# mySatellite.net
KiCad netlist of a schematic drawn in EAGLE
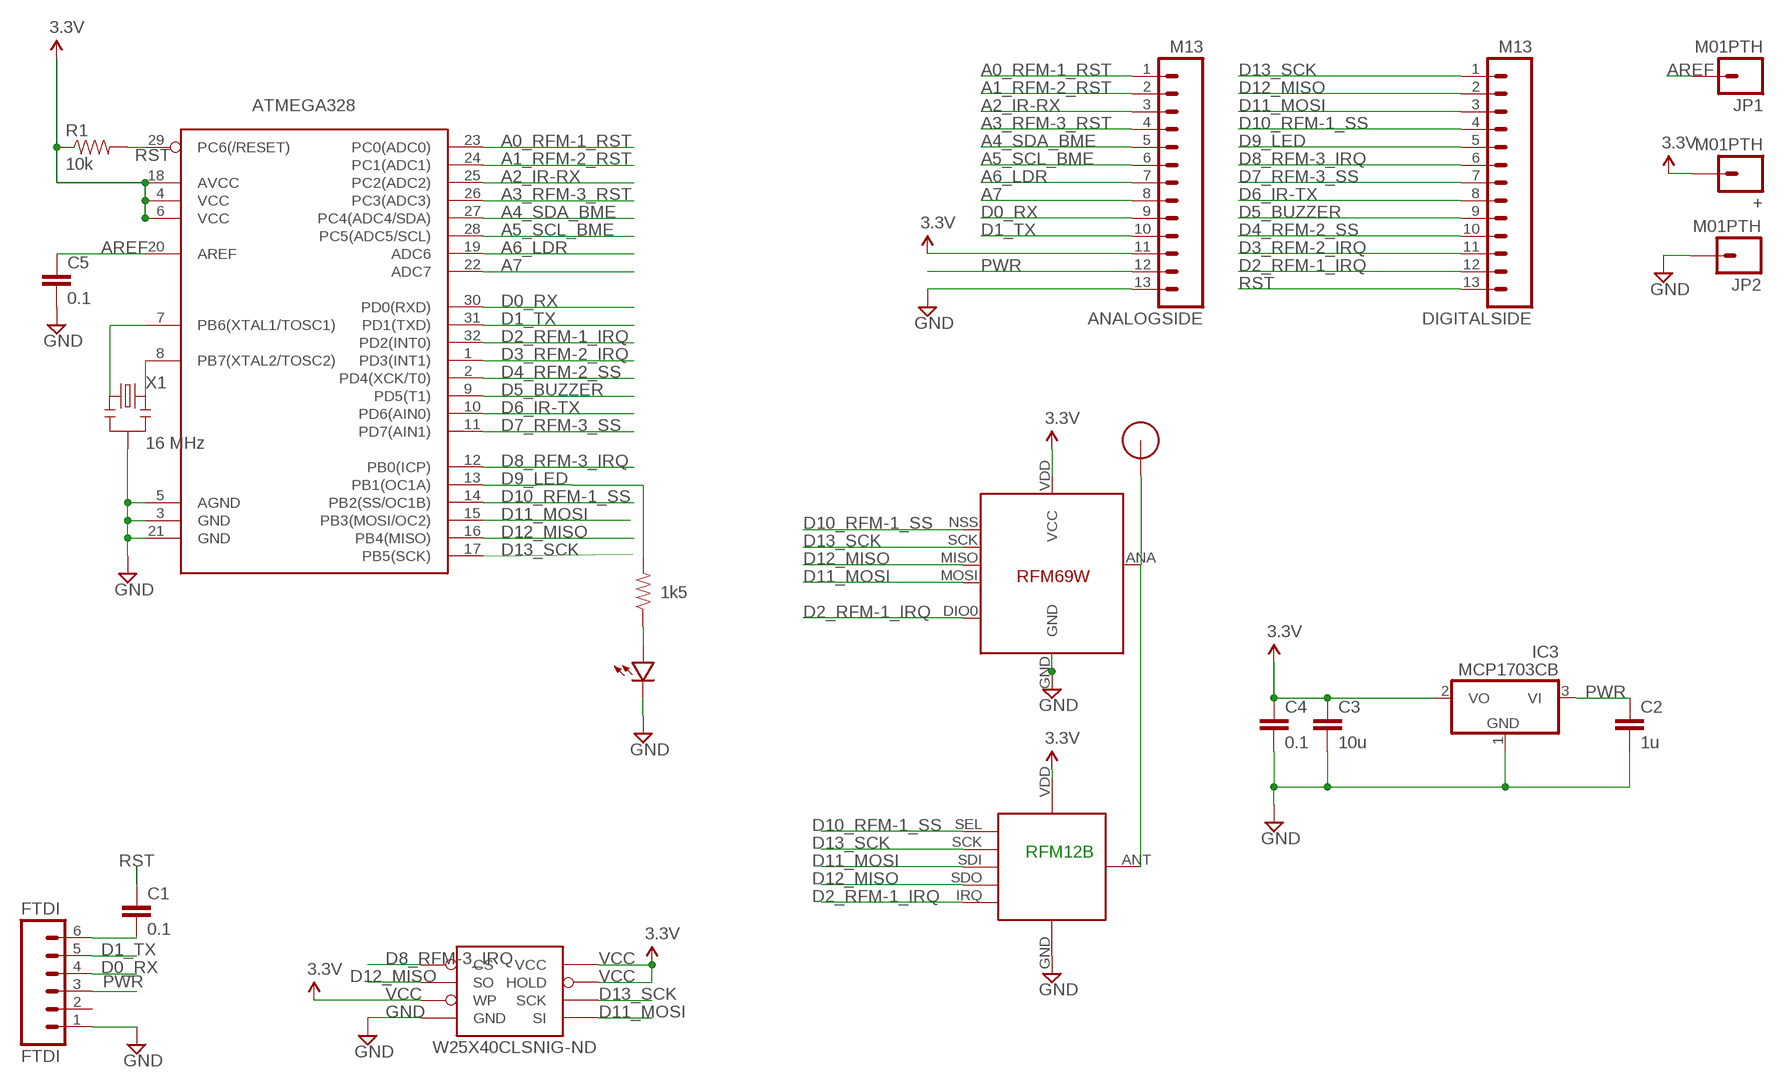
[diagram p0: schematic, sheet 1]

(export (version "E")
  (design (tool "Eeschema 10.0.6"))
  (components
    (comp (ref "+")
      (value "M01PTH")
      (footprint "eagle-import:1X01")
      (libsource (lib "eagle-import") (part "M01PTH"))
    )
    (comp (ref "ANALOGSIDE")
      (value "M13")
      (footprint "eagle-import:1X13")
      (libsource (lib "eagle-import") (part "M13"))
    )
    (comp (ref "ATMEGA328")
      (value "ATMega-328")
      (footprint "eagle-import:TQFP32-08")
      (libsource (lib "eagle-import") (part "ATMEGA168/328TQFP32"))
    )
    (comp (ref "C1")
      (value "0.1")
      (footprint "eagle-import:0603-CAP")
      (libsource (lib "eagle-import") (part "CAP0603-CAP"))
    )
    (comp (ref "C2")
      (value "1u")
      (footprint "eagle-import:0603-CAP")
      (libsource (lib "eagle-import") (part "CAP0603-CAP"))
    )
    (comp (ref "C3")
      (value "10u")
      (footprint "eagle-import:0805-CAP")
      (libsource (lib "eagle-import") (part "CAP0805-CAP"))
    )
    (comp (ref "C4")
      (value "0.1")
      (footprint "eagle-import:0603-CAP")
      (libsource (lib "eagle-import") (part "CAP0603-CAP"))
    )
    (comp (ref "C5")
      (value "0.1")
      (footprint "eagle-import:0603-CAP")
      (libsource (lib "eagle-import") (part "CAP0603-CAP"))
    )
    (comp (ref "DIGITALSIDE")
      (value "M13")
      (footprint "eagle-import:1X13")
      (libsource (lib "eagle-import") (part "M13"))
    )
    (comp (ref "FTDI")
      (value "FTDI")
      (footprint "eagle-import:1X06")
      (libsource (lib "eagle-import") (part "M06SIP"))
    )
    (comp (ref "IC3")
      (value "MCP1703CB")
      (footprint "eagle-import:SOT23")
      (libsource (lib "eagle-import") (part "MCP1703CB"))
    )
    (comp (ref "JP1")
      (value "M01PTH")
      (footprint "eagle-import:1X01")
      (libsource (lib "eagle-import") (part "M01PTH"))
    )
    (comp (ref "JP2")
      (value "M01PTH")
      (footprint "eagle-import:1X01")
      (libsource (lib "eagle-import") (part "M01PTH"))
    )
    (comp (ref "R1")
      (value "10k")
      (footprint "eagle-import:0603-RES")
      (libsource (lib "eagle-import") (part "RESISTOR0603-RES"))
    )
    (comp (ref "R2")
      (value "1k5")
      (footprint "eagle-import:0603-RES")
      (libsource (lib "eagle-import") (part "RESISTOR0603-RES"))
    )
    (comp (ref "RFM12B")
      (value "RFM12B_MINPADS")
      (footprint "eagle-import:RFM12B-MINPADS")
      (libsource (lib "eagle-import") (part "RFM12B_MINPADS"))
    )
    (comp (ref "U$1")
      (value "RFM12B_ANTENNA")
      (footprint "eagle-import:RFM12B-ANTENNA")
      (libsource (lib "eagle-import") (part "RFM12B_ANTENNA"))
    )
    (comp (ref "U$2")
      (value "LED0603")
      (footprint "eagle-import:0603-LED")
      (libsource (lib "eagle-import") (part "LED0603"))
    )
    (comp (ref "U$5")
      (value "RFM69")
      (footprint "eagle-import:RFM69W-MINPADS")
      (libsource (lib "eagle-import") (part "RFM69"))
    )
    (comp (ref "W25X40CLSNIG-ND")
      (value "AT25F512BWIDE_5.3MM")
      (footprint "eagle-import:SO08WIDE")
      (libsource (lib "eagle-import") (part "AT25F512BWIDE_5.3MM"))
    )
    (comp (ref "X1")
      (value "16 MHz")
      (footprint "eagle-import:RESONATOR-SMD")
      (libsource (lib "eagle-import") (part "RESONATORSMD"))
    )
  )
  (nets
    (net (code "1") (name "/A0_RFM-1_RST") (class "Default")
      (node (ref "ANALOGSIDE") (pin "1") (pinfunction "1_1") (pintype "passive"))
      (node (ref "ATMEGA328") (pin "23") (pinfunction "PC0(ADC0)_23") (pintype "bidirectional"))
    )
    (net (code "2") (name "/A1_RFM-2_RST") (class "Default")
      (node (ref "ANALOGSIDE") (pin "2") (pinfunction "2_2") (pintype "passive"))
      (node (ref "ATMEGA328") (pin "24") (pinfunction "PC1(ADC1)_24") (pintype "bidirectional"))
    )
    (net (code "3") (name "/A2_IR-RX") (class "Default")
      (node (ref "ANALOGSIDE") (pin "3") (pinfunction "3_3") (pintype "passive"))
      (node (ref "ATMEGA328") (pin "25") (pinfunction "PC2(ADC2)_25") (pintype "bidirectional"))
    )
    (net (code "4") (name "/A3_RFM-3_RST") (class "Default")
      (node (ref "ANALOGSIDE") (pin "4") (pinfunction "4_4") (pintype "passive"))
      (node (ref "ATMEGA328") (pin "26") (pinfunction "PC3(ADC3)_26") (pintype "bidirectional"))
    )
    (net (code "5") (name "/A4_SDA_BME") (class "Default")
      (node (ref "ANALOGSIDE") (pin "5") (pinfunction "5_5") (pintype "passive"))
      (node (ref "ATMEGA328") (pin "27") (pinfunction "PC4(ADC4/SDA)_27") (pintype "bidirectional"))
    )
    (net (code "6") (name "/A5_SCL_BME") (class "Default")
      (node (ref "ANALOGSIDE") (pin "6") (pinfunction "6_6") (pintype "passive"))
      (node (ref "ATMEGA328") (pin "28") (pinfunction "PC5(ADC5/SCL)_28") (pintype "bidirectional"))
    )
    (net (code "7") (name "/A6_LDR") (class "Default")
      (node (ref "ANALOGSIDE") (pin "7") (pinfunction "7_7") (pintype "passive"))
      (node (ref "ATMEGA328") (pin "19") (pinfunction "ADC6_19") (pintype "bidirectional"))
    )
    (net (code "8") (name "/A7") (class "Default")
      (node (ref "ANALOGSIDE") (pin "8") (pinfunction "8_8") (pintype "passive"))
      (node (ref "ATMEGA328") (pin "22") (pinfunction "ADC7_22") (pintype "bidirectional"))
    )
    (net (code "9") (name "/AREF") (class "Default")
      (node (ref "ATMEGA328") (pin "20") (pinfunction "AREF_20") (pintype "bidirectional"))
      (node (ref "C5") (pin "1") (pinfunction "1_1") (pintype "passive"))
      (node (ref "JP1") (pin "1") (pinfunction "1_1") (pintype "passive"))
    )
    (net (code "10") (name "/D0_RX") (class "Default")
      (node (ref "ANALOGSIDE") (pin "9") (pinfunction "9_9") (pintype "passive"))
      (node (ref "ATMEGA328") (pin "30") (pinfunction "PD0(RXD)_30") (pintype "bidirectional"))
      (node (ref "FTDI") (pin "4") (pinfunction "4_4") (pintype "passive"))
    )
    (net (code "11") (name "/D1_TX") (class "Default")
      (node (ref "ANALOGSIDE") (pin "10") (pinfunction "10_10") (pintype "passive"))
      (node (ref "ATMEGA328") (pin "31") (pinfunction "PD1(TXD)_31") (pintype "bidirectional"))
      (node (ref "FTDI") (pin "5") (pinfunction "5_5") (pintype "passive"))
    )
    (net (code "12") (name "/D2_RFM-1_IRQ") (class "Default")
      (node (ref "ATMEGA328") (pin "32") (pinfunction "PD2(INT0)_32") (pintype "bidirectional"))
      (node (ref "DIGITALSIDE") (pin "12") (pinfunction "12_12") (pintype "passive"))
      (node (ref "RFM12B") (pin "IRQ") (pinfunction "IRQ_IRQ") (pintype "bidirectional"))
      (node (ref "U$5") (pin "DIO0") (pinfunction "DIO0_DIO0") (pintype "open_collector"))
    )
    (net (code "13") (name "/D3_RFM-2_IRQ") (class "Default")
      (node (ref "ATMEGA328") (pin "1") (pinfunction "PD3(INT1)_1") (pintype "bidirectional"))
      (node (ref "DIGITALSIDE") (pin "11") (pinfunction "11_11") (pintype "passive"))
    )
    (net (code "14") (name "/D4_RFM-2_SS") (class "Default")
      (node (ref "ATMEGA328") (pin "2") (pinfunction "PD4(XCK/T0)_2") (pintype "bidirectional"))
      (node (ref "DIGITALSIDE") (pin "10") (pinfunction "10_10") (pintype "passive"))
    )
    (net (code "15") (name "/D5_BUZZER") (class "Default")
      (node (ref "ATMEGA328") (pin "9") (pinfunction "PD5(T1)_9") (pintype "bidirectional"))
      (node (ref "DIGITALSIDE") (pin "9") (pinfunction "9_9") (pintype "passive"))
    )
    (net (code "16") (name "/D6_IR-TX") (class "Default")
      (node (ref "ATMEGA328") (pin "10") (pinfunction "PD6(AIN0)_10") (pintype "bidirectional"))
      (node (ref "DIGITALSIDE") (pin "8") (pinfunction "8_8") (pintype "passive"))
    )
    (net (code "17") (name "/D7_RFM-3_SS") (class "Default")
      (node (ref "ATMEGA328") (pin "11") (pinfunction "PD7(AIN1)_11") (pintype "bidirectional"))
      (node (ref "DIGITALSIDE") (pin "7") (pinfunction "7_7") (pintype "passive"))
    )
    (net (code "18") (name "/D8_RFM-3_IRQ") (class "Default")
      (node (ref "ATMEGA328") (pin "12") (pinfunction "PB0(ICP)_12") (pintype "bidirectional"))
      (node (ref "DIGITALSIDE") (pin "6") (pinfunction "6_6") (pintype "passive"))
      (node (ref "W25X40CLSNIG-ND") (pin "1") (pinfunction "CS_1") (pintype "bidirectional"))
    )
    (net (code "19") (name "/D9_LED") (class "Default")
      (node (ref "ATMEGA328") (pin "13") (pinfunction "PB1(OC1A)_13") (pintype "bidirectional"))
      (node (ref "DIGITALSIDE") (pin "5") (pinfunction "5_5") (pintype "passive"))
      (node (ref "R2") (pin "2") (pinfunction "2_2") (pintype "passive"))
    )
    (net (code "20") (name "/D10_RFM-1_SS") (class "Default")
      (node (ref "ATMEGA328") (pin "14") (pinfunction "PB2(SS/OC1B)_14") (pintype "bidirectional"))
      (node (ref "DIGITALSIDE") (pin "4") (pinfunction "4_4") (pintype "passive"))
      (node (ref "RFM12B") (pin "SEL") (pinfunction "SEL_SEL") (pintype "bidirectional"))
      (node (ref "U$5") (pin "NSS") (pinfunction "SEL_NSS") (pintype "input"))
    )
    (net (code "21") (name "/D11_MOSI") (class "Default")
      (node (ref "ATMEGA328") (pin "15") (pinfunction "PB3(MOSI/OC2)_15") (pintype "bidirectional"))
      (node (ref "DIGITALSIDE") (pin "3") (pinfunction "3_3") (pintype "passive"))
      (node (ref "RFM12B") (pin "SDI") (pinfunction "SDI/MOSI_SDI") (pintype "bidirectional"))
      (node (ref "U$5") (pin "MOSI") (pinfunction "MOSI_MOSI") (pintype "output"))
      (node (ref "W25X40CLSNIG-ND") (pin "5") (pinfunction "SI_5") (pintype "bidirectional"))
    )
    (net (code "22") (name "/D12_MISO") (class "Default")
      (node (ref "ATMEGA328") (pin "16") (pinfunction "PB4(MISO)_16") (pintype "bidirectional"))
      (node (ref "DIGITALSIDE") (pin "2") (pinfunction "2_2") (pintype "passive"))
      (node (ref "RFM12B") (pin "SDO") (pinfunction "SDO/MISO_SDO") (pintype "bidirectional"))
      (node (ref "U$5") (pin "MISO") (pinfunction "MISO_MISO") (pintype "input"))
      (node (ref "W25X40CLSNIG-ND") (pin "2") (pinfunction "SO_2") (pintype "bidirectional"))
    )
    (net (code "23") (name "/D13_SCK") (class "Default")
      (node (ref "ATMEGA328") (pin "17") (pinfunction "PB5(SCK)_17") (pintype "bidirectional"))
      (node (ref "DIGITALSIDE") (pin "1") (pinfunction "1_1") (pintype "passive"))
      (node (ref "RFM12B") (pin "SCK") (pinfunction "SCK_SCK") (pintype "bidirectional"))
      (node (ref "U$5") (pin "SCK") (pinfunction "SCK_SCK") (pintype "input"))
      (node (ref "W25X40CLSNIG-ND") (pin "6") (pinfunction "SCK_6") (pintype "bidirectional"))
    )
    (net (code "24") (name "/PWR") (class "Default")
      (node (ref "ANALOGSIDE") (pin "12") (pinfunction "12_12") (pintype "passive"))
      (node (ref "C2") (pin "1") (pinfunction "1_1") (pintype "passive"))
      (node (ref "FTDI") (pin "3") (pinfunction "3_3") (pintype "passive"))
      (node (ref "IC3") (pin "3") (pinfunction "VI_3") (pintype "input"))
    )
    (net (code "25") (name "/RST") (class "Default")
      (node (ref "ATMEGA328") (pin "29") (pinfunction "PC6(/RESET)_29") (pintype "bidirectional"))
      (node (ref "C1") (pin "1") (pinfunction "1_1") (pintype "passive"))
      (node (ref "DIGITALSIDE") (pin "13") (pinfunction "13_13") (pintype "passive"))
      (node (ref "R1") (pin "2") (pinfunction "2_2") (pintype "passive"))
    )
    (net (code "26") (name "3.3V") (class "Default")
      (node (ref "+") (pin "1") (pinfunction "1_1") (pintype "passive"))
      (node (ref "ANALOGSIDE") (pin "11") (pinfunction "11_11") (pintype "passive"))
      (node (ref "ATMEGA328") (pin "18") (pinfunction "AVCC_18") (pintype "bidirectional"))
      (node (ref "ATMEGA328") (pin "4") (pinfunction "VCC_4") (pintype "bidirectional"))
      (node (ref "ATMEGA328") (pin "6") (pinfunction "VCC_6") (pintype "bidirectional"))
      (node (ref "C3") (pin "1") (pinfunction "1_1") (pintype "passive"))
      (node (ref "C4") (pin "1") (pinfunction "1_1") (pintype "passive"))
      (node (ref "IC3") (pin "2") (pinfunction "VO_2") (pintype "passive"))
      (node (ref "R1") (pin "1") (pinfunction "1_1") (pintype "passive"))
      (node (ref "RFM12B") (pin "VDD") (pinfunction "VDD_VDD") (pintype "bidirectional"))
      (node (ref "U$5") (pin "VDD") (pinfunction "VCC_VDD") (pintype "power_in"))
      (node (ref "W25X40CLSNIG-ND") (pin "3") (pinfunction "WP_3") (pintype "bidirectional"))
      (node (ref "W25X40CLSNIG-ND") (pin "7") (pinfunction "HOLD_7") (pintype "bidirectional"))
      (node (ref "W25X40CLSNIG-ND") (pin "8") (pinfunction "VCC_8") (pintype "bidirectional"))
    )
    (net (code "27") (name "GND") (class "Default")
      (node (ref "ANALOGSIDE") (pin "13") (pinfunction "13_13") (pintype "passive"))
      (node (ref "ATMEGA328") (pin "21") (pinfunction "GND_21") (pintype "bidirectional"))
      (node (ref "ATMEGA328") (pin "3") (pinfunction "GND_3") (pintype "bidirectional"))
      (node (ref "ATMEGA328") (pin "5") (pinfunction "AGND_5") (pintype "bidirectional"))
      (node (ref "C2") (pin "2") (pinfunction "2_2") (pintype "passive"))
      (node (ref "C3") (pin "2") (pinfunction "2_2") (pintype "passive"))
      (node (ref "C4") (pin "2") (pinfunction "2_2") (pintype "passive"))
      (node (ref "C5") (pin "2") (pinfunction "2_2") (pintype "passive"))
      (node (ref "FTDI") (pin "1") (pinfunction "1_1") (pintype "passive"))
      (node (ref "IC3") (pin "1") (pinfunction "GND_1") (pintype "passive"))
      (node (ref "JP2") (pin "1") (pinfunction "1_1") (pintype "passive"))
      (node (ref "RFM12B") (pin "GND") (pinfunction "GND_GND") (pintype "bidirectional"))
      (node (ref "U$2") (pin "MINUS") (pinfunction "MINUS_MINUS") (pintype "passive"))
      (node (ref "U$5") (pin "GND") (pinfunction "GND_GND") (pintype "power_in"))
      (node (ref "W25X40CLSNIG-ND") (pin "4") (pinfunction "GND_4") (pintype "bidirectional"))
      (node (ref "X1") (pin "2") (pinfunction "2_2") (pintype "passive"))
    )
    (net (code "28") (name "Net-(ATMEGA328-PB6(XTAL1{slash}TOSC1))") (class "Default")
      (node (ref "ATMEGA328") (pin "7") (pinfunction "PB6(XTAL1/TOSC1)_7") (pintype "bidirectional"))
      (node (ref "X1") (pin "1") (pinfunction "1_1") (pintype "passive"))
    )
    (net (code "29") (name "Net-(ATMEGA328-PB7(XTAL2{slash}TOSC2))") (class "Default")
      (node (ref "ATMEGA328") (pin "8") (pinfunction "PB7(XTAL2/TOSC2)_8") (pintype "bidirectional"))
      (node (ref "X1") (pin "3") (pinfunction "3_3") (pintype "passive"))
    )
    (net (code "30") (name "Net-(C1-Pad2)") (class "Default")
      (node (ref "C1") (pin "2") (pinfunction "2_2") (pintype "passive"))
      (node (ref "FTDI") (pin "6") (pinfunction "6_6") (pintype "passive"))
    )
    (net (code "31") (name "Net-(R2-Pad1)") (class "Default")
      (node (ref "R2") (pin "1") (pinfunction "1_1") (pintype "passive"))
      (node (ref "U$2") (pin "PLUS") (pinfunction "PLUS_PLUS") (pintype "passive"))
    )
    (net (code "32") (name "Net-(U$1-1)") (class "Default")
      (node (ref "RFM12B") (pin "ANT") (pinfunction "ANT_ANT") (pintype "bidirectional"))
      (node (ref "U$1") (pin "P$1") (pinfunction "1_P$1") (pintype "bidirectional"))
      (node (ref "U$5") (pin "ANA") (pinfunction "ANT_ANA") (pintype "passive"))
    )
    (net (code "33") (name "unconnected-(FTDI-Pad2)") (class "Default")
      (node (ref "FTDI") (pin "2") (pinfunction "2_2") (pintype "passive"))
    )
  )
)
